# cpx-synth1-jacks.net
KiCad netlist of a schematic drawn in EAGLE
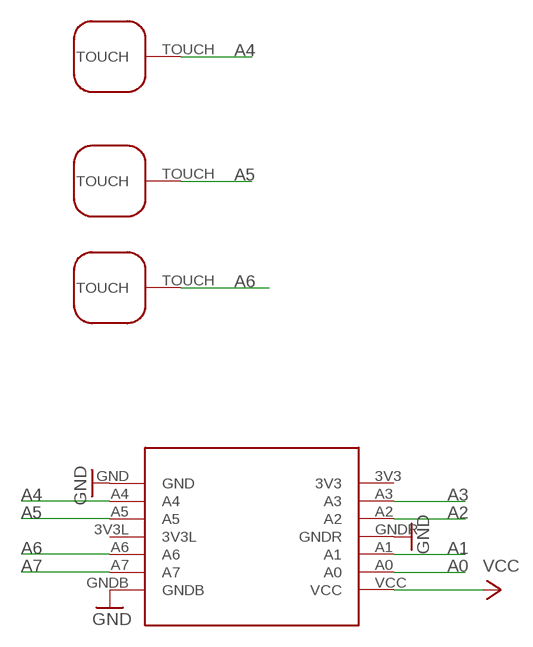
[diagram p0: schematic, sheet 1]

(export (version "E")
  (design (tool "Eeschema 10.0.6"))
  (components
    (comp (ref "T1")
      (value "TOUCHPADROUND1")
      (footprint "eagle-import:TOUCHPAD1")
      (libsource (lib "eagle-import") (part "TOUCHPADROUND1"))
    )
    (comp (ref "T2")
      (value "TOUCHPADROUND1")
      (footprint "eagle-import:TOUCHPAD1")
      (libsource (lib "eagle-import") (part "TOUCHPADROUND1"))
    )
    (comp (ref "T3")
      (value "TOUCHPADROUND1")
      (footprint "eagle-import:TOUCHPAD1")
      (libsource (lib "eagle-import") (part "TOUCHPADROUND1"))
    )
    (comp (ref "U1")
      (value "CIRCUITPLAYGROUNDEXPRESS")
      (footprint "eagle-import:CIRCUITPLAYGROUNDEXPRESS")
      (libsource (lib "eagle-import") (part "CIRCUITPLAYGROUNDEXPRESS"))
    )
  )
  (nets
    (net (code "1") (name "/A0") (class "Default")
      (node (ref "U1") (pin "A0") (pinfunction "A0_A0") (pintype "bidirectional"))
    )
    (net (code "2") (name "/A1") (class "Default")
      (node (ref "U1") (pin "A1") (pinfunction "A1_A1") (pintype "bidirectional"))
    )
    (net (code "3") (name "/A2") (class "Default")
      (node (ref "U1") (pin "A2") (pinfunction "A2_A2") (pintype "bidirectional"))
    )
    (net (code "4") (name "/A3") (class "Default")
      (node (ref "U1") (pin "A3") (pinfunction "A3_A3") (pintype "bidirectional"))
    )
    (net (code "5") (name "/A4") (class "Default")
      (node (ref "T3") (pin "TOUCH") (pinfunction "TOUCH_TOUCH") (pintype "bidirectional"))
      (node (ref "U1") (pin "A4") (pinfunction "A4_A4") (pintype "bidirectional"))
    )
    (net (code "6") (name "/A5") (class "Default")
      (node (ref "T2") (pin "TOUCH") (pinfunction "TOUCH_TOUCH") (pintype "bidirectional"))
      (node (ref "U1") (pin "A5") (pinfunction "A5_A5") (pintype "bidirectional"))
    )
    (net (code "7") (name "/A6") (class "Default")
      (node (ref "T1") (pin "TOUCH") (pinfunction "TOUCH_TOUCH") (pintype "bidirectional"))
      (node (ref "U1") (pin "A6") (pinfunction "A6_A6") (pintype "bidirectional"))
    )
    (net (code "8") (name "/A7") (class "Default")
      (node (ref "U1") (pin "A7") (pinfunction "A7_A7") (pintype "bidirectional"))
    )
    (net (code "9") (name "GND") (class "Default")
      (node (ref "U1") (pin "GND") (pinfunction "GND_GND") (pintype "bidirectional"))
      (node (ref "U1") (pin "GNDB") (pinfunction "GNDB_GNDB") (pintype "bidirectional"))
      (node (ref "U1") (pin "GNDR") (pinfunction "GNDR_GNDR") (pintype "bidirectional"))
    )
    (net (code "10") (name "VCC") (class "Default")
      (node (ref "U1") (pin "VCC") (pinfunction "VCC_VCC") (pintype "bidirectional"))
    )
    (net (code "11") (name "unconnected-(U1-Pad3V3)") (class "Default")
      (node (ref "U1") (pin "3V3") (pinfunction "3V3_3V3") (pintype "bidirectional"))
    )
    (net (code "12") (name "unconnected-(U1-Pad3V3L)") (class "Default")
      (node (ref "U1") (pin "3V3L") (pinfunction "3V3L_3V3L") (pintype "bidirectional"))
    )
  )
)
